# TIDA-010933-DCDC-CLLLC.net
KiCad netlist of a schematic drawn in Altium Designer
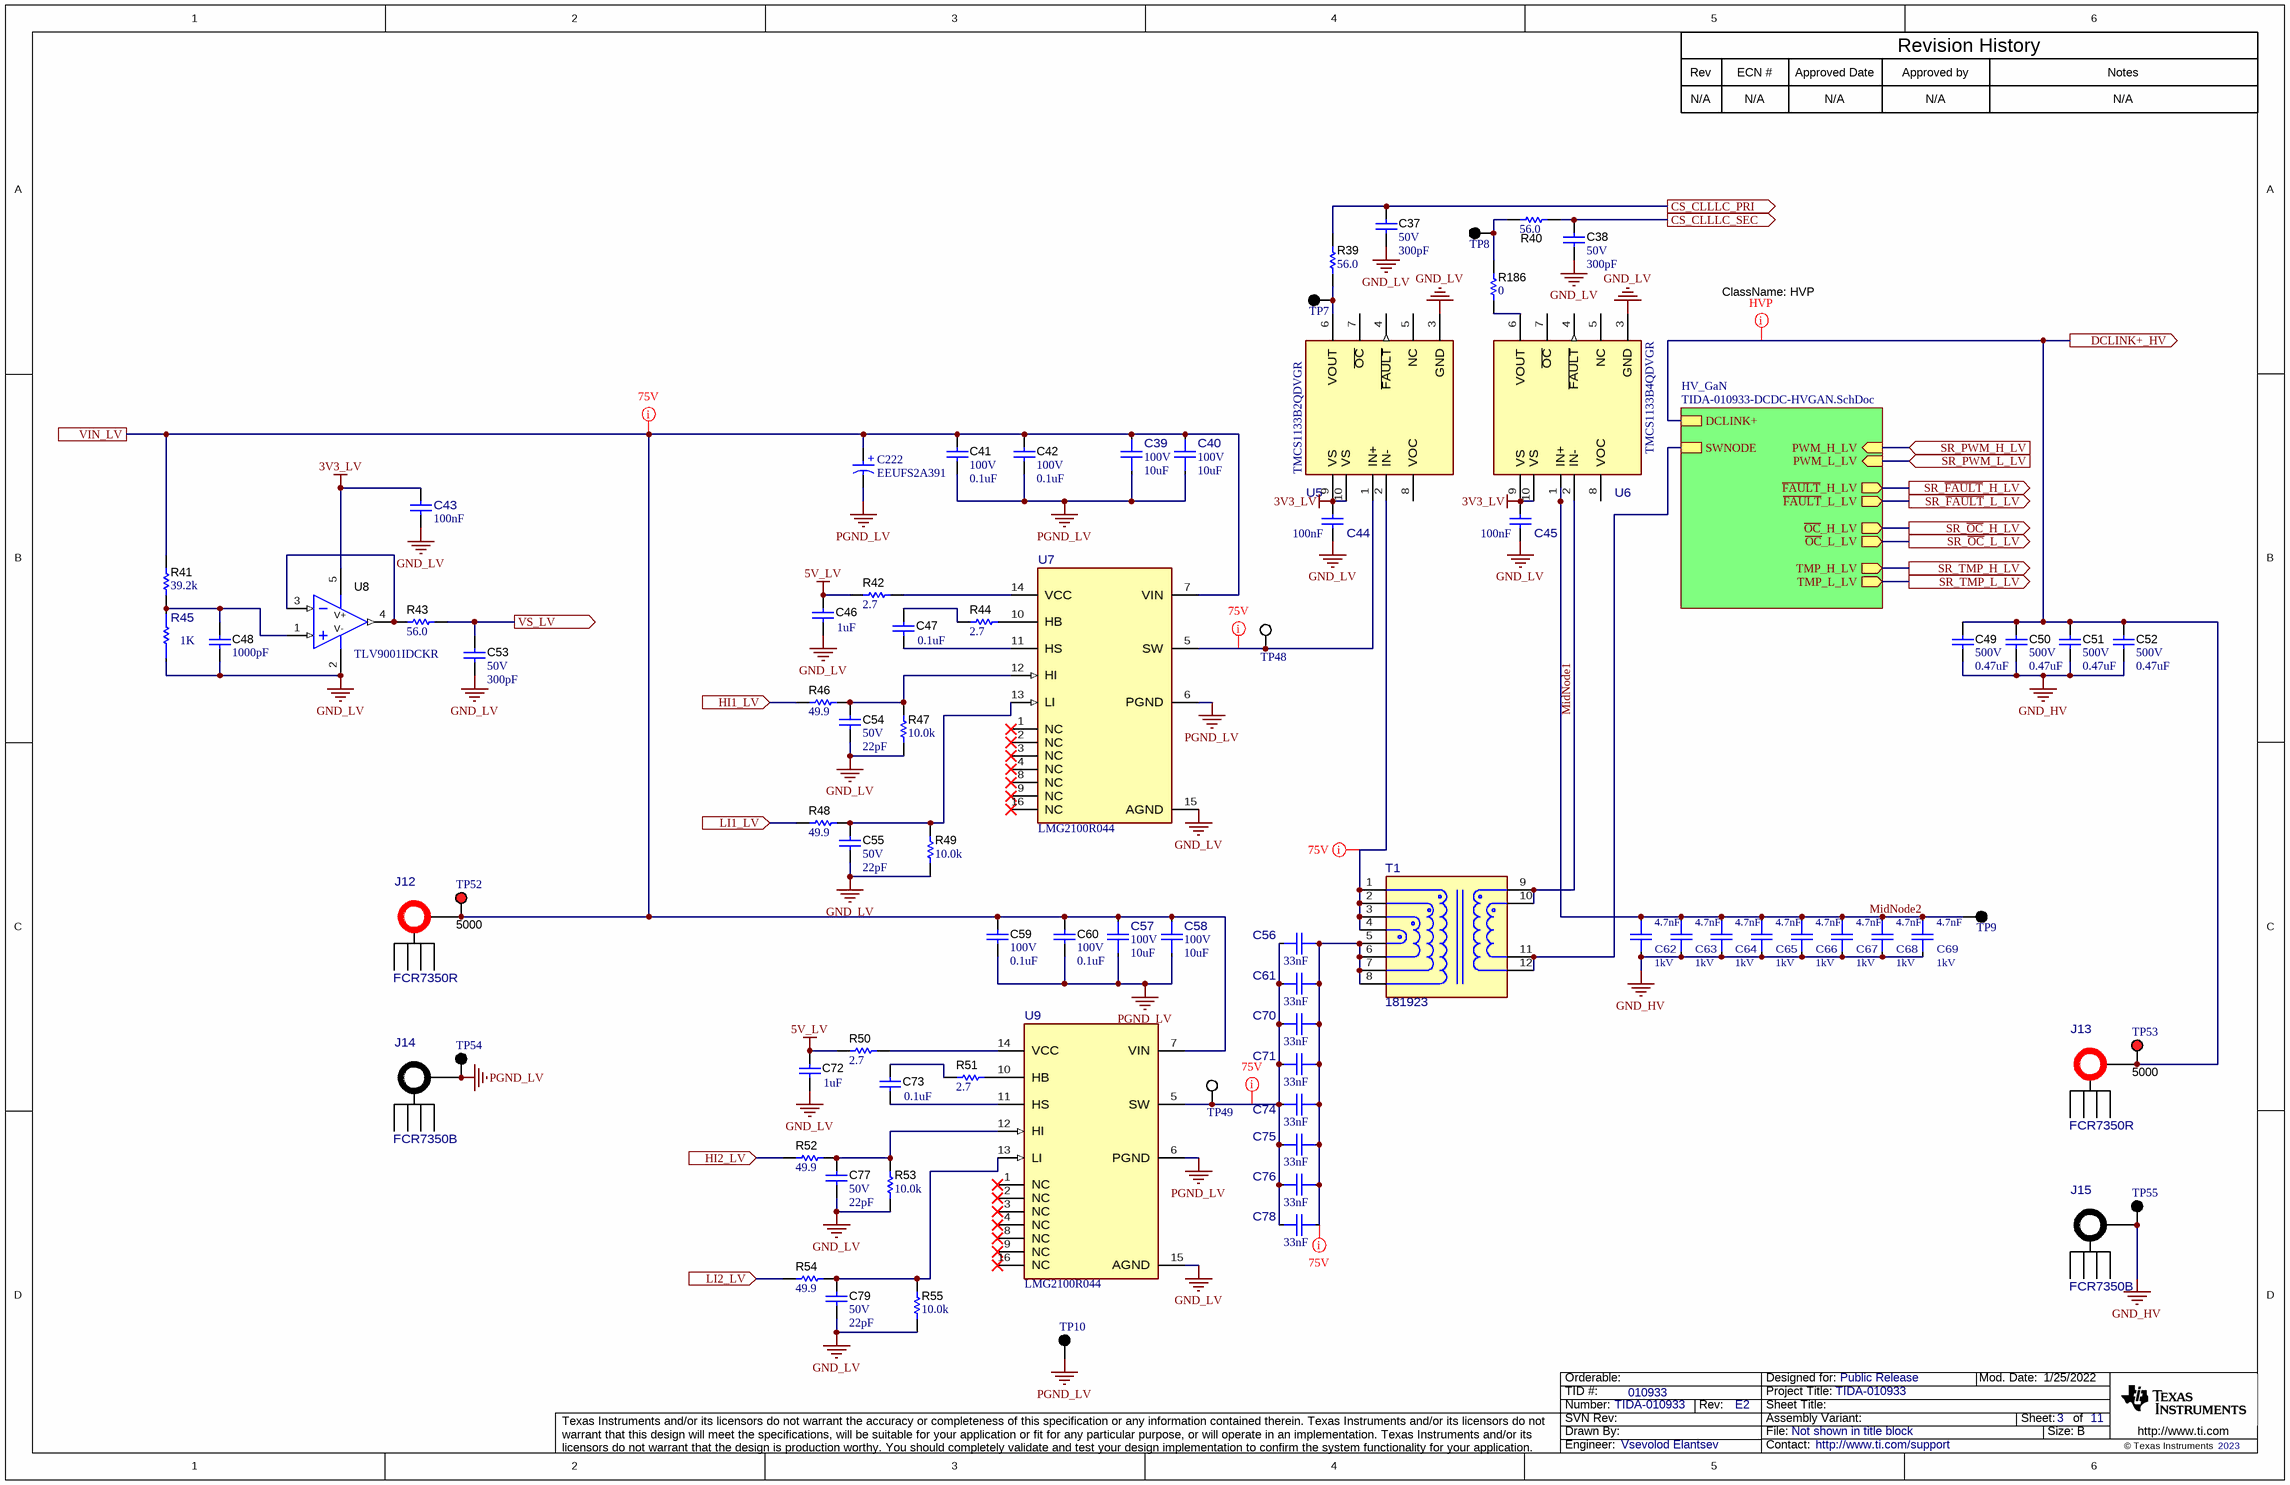
[diagram p0: TIDA-010933-DCDC-CLLLC.SchDoc]

(export (version "E")
  (design (tool "Eeschema 10.0.6"))
  (components
    (comp (ref "C37")
      (value "GRM1555C1H301JA01D")
      (footprint "0402")
      (description "CAP, CERM, 300 pF, 50 V, +/- 5%, C0G/NP0, 0402")
      (fields
        (field (name "MANUFACTURER") "MuRata")
        (field (name "VDC_V") "50V")
        (field (name "VALUEDISPLAYED") "300pF")
        (field (name "PUBLISHER") "Texas Instruments")
      )
      (libsource (lib "Altium Vault - TI") (part "Capacitor"))
    )
    (comp (ref "C38")
      (value "GRM1555C1H301JA01D")
      (footprint "0402")
      (description "CAP, CERM, 300 pF, 50 V, +/- 5%, C0G/NP0, 0402")
      (fields
        (field (name "MANUFACTURER") "MuRata")
        (field (name "VDC_V") "50V")
        (field (name "VALUEDISPLAYED") "300pF")
        (field (name "PUBLISHER") "Texas Instruments")
      )
      (libsource (lib "Altium Vault - TI") (part "Capacitor"))
    )
    (comp (ref "C39")
      (value "C3225X7R2A106K250AC")
      (footprint "FP-C3225X7R2A106K250AC_1210-MFG")
      (description "10 µF ±10% 100V Ceramic Capacitor X7R 1210 (3225 Metric)")
      (fields
        (field (name "DIGIKEY PART NUMBER") "445-C3225X7R2A106K250ACCT-ND")
        (field (name "MOUSER PART NUMBER") "810-C3225X7R2A106K25")
        (field (name "VDC_V") "100V")
        (field (name "VALUEDISPLAYED") "10uF")
      )
      (libsource (lib "Altium Vault - TI") (part "SYM-C3225X7R2A106K250AC"))
    )
    (comp (ref "C40")
      (value "C3225X7R2A106K250AC")
      (footprint "FP-C3225X7R2A106K250AC_1210-MFG")
      (description "10 µF ±10% 100V Ceramic Capacitor X7R 1210 (3225 Metric)")
      (fields
        (field (name "DIGIKEY PART NUMBER") "445-C3225X7R2A106K250ACCT-ND")
        (field (name "MOUSER PART NUMBER") "810-C3225X7R2A106K25")
        (field (name "VDC_V") "100V")
        (field (name "VALUEDISPLAYED") "10uF")
      )
      (libsource (lib "Altium Vault - TI") (part "SYM-C3225X7R2A106K250AC"))
    )
    (comp (ref "C41")
      (value "GRM155R62A104KE14D")
      (footprint "0402")
      (description "CAP, CERM, 0.1 uF, 100 V, +/- 10%, X5R, 0402")
      (fields
        (field (name "MANUFACTURER") "MuRata")
        (field (name "VDC_V") "100V")
        (field (name "VALUEDISPLAYED") "0.1uF")
        (field (name "PUBLISHER") "Texas Instruments")
      )
      (libsource (lib "Altium Vault - TI") (part "Capacitor"))
    )
    (comp (ref "C42")
      (value "GRM155R62A104KE14D")
      (footprint "0402")
      (description "CAP, CERM, 0.1 uF, 100 V, +/- 10%, X5R, 0402")
      (fields
        (field (name "MANUFACTURER") "MuRata")
        (field (name "VDC_V") "100V")
        (field (name "VALUEDISPLAYED") "0.1uF")
        (field (name "PUBLISHER") "Texas Instruments")
      )
      (libsource (lib "Altium Vault - TI") (part "Capacitor"))
    )
    (comp (ref "C43")
      (value "CL10B104KB8NNNC")
      (footprint "FP-CL10B104KB8NNNC_0603-IPC_B")
      (description "CAP CER 0.1UF 50V X7R 0603")
      (fields (field (name "CAP_F") "100nF") (field (name "MANUFACTURER") "Samsung"))
      (libsource (lib "Altium Vault - TI") (part "SYM-CAPACITOR"))
    )
    (comp (ref "C44")
      (value "CL10B104KB8NNNC")
      (footprint "FP-CL10B104KB8NNNC_0603-IPC_B")
      (description "CAP CER 0.1UF 50V X7R 0603")
      (fields (field (name "CAP_F") "100nF") (field (name "MANUFACTURER") "Samsung"))
      (libsource (lib "Altium Vault - TI") (part "SYM-CAPACITOR"))
    )
    (comp (ref "C45")
      (value "CL10B104KB8NNNC")
      (footprint "FP-CL10B104KB8NNNC_0603-IPC_B")
      (description "CAP CER 0.1UF 50V X7R 0603")
      (fields (field (name "CAP_F") "100nF") (field (name "MANUFACTURER") "Samsung"))
      (libsource (lib "Altium Vault - TI") (part "SYM-CAPACITOR"))
    )
    (comp (ref "C46")
      (value "GRM155R61E105KA12D")
      (footprint "0402")
      (description "CAP, CERM, 1 uF, 25 V, +/- 10%, X5R, 0402")
      (fields
        (field (name "MANUFACTURER") "MuRata")
        (field (name "VALUEDISPLAYED") "1uF")
        (field (name "PUBLISHER") "Texas Instruments")
      )
      (libsource (lib "Altium Vault - TI") (part "Capacitor"))
    )
    (comp (ref "C47")
      (value "GRM155R71E104KE14D")
      (footprint "0402")
      (description "CAP, CERM, 0.1 uF, 25 V, +/- 10%, X7R, 0402")
      (fields
        (field (name "MANUFACTURER") "MuRata")
        (field (name "VALUEDISPLAYED") "0.1uF")
        (field (name "PUBLISHER") "Texas Instruments")
      )
      (libsource (lib "Altium Vault - TI") (part "Capacitor"))
    )
    (comp (ref "C48")
      (value "CC0603JRNPO8BN102")
      (footprint "0603")
      (description "CAP, CERM, 1000 pF, 25 V,+/- 5%, C0G/NP0, 0603")
      (fields (field (name "VALUEDISPLAYED") "1000pF") (field (name "MANUFACTURER") "Yageo"))
      (libsource (lib "Altium Vault - TI") (part "Capacitor"))
    )
    (comp (ref "C49")
      (value "1812Y5000474KXTWS2")
      (footprint "1812_254")
      (description "CAP, CERM, 0.47 uF, 500 V, +/- 10%, X7R, 1812")
      (fields
        (field (name "MANUFACTURER") "Knowles Capacitors")
        (field (name "VDC_V") "500V")
        (field (name "VALUEDISPLAYED") "0.47uF")
        (field (name "PUBLISHER") "Texas Instruments")
      )
      (libsource (lib "Altium Vault - TI") (part "Capacitor"))
    )
    (comp (ref "C50")
      (value "1812Y5000474KXTWS2")
      (footprint "1812_254")
      (description "CAP, CERM, 0.47 uF, 500 V, +/- 10%, X7R, 1812")
      (fields
        (field (name "MANUFACTURER") "Knowles Capacitors")
        (field (name "VDC_V") "500V")
        (field (name "VALUEDISPLAYED") "0.47uF")
        (field (name "PUBLISHER") "Texas Instruments")
      )
      (libsource (lib "Altium Vault - TI") (part "Capacitor"))
    )
    (comp (ref "C51")
      (value "1812Y5000474KXTWS2")
      (footprint "1812_254")
      (description "CAP, CERM, 0.47 uF, 500 V, +/- 10%, X7R, 1812")
      (fields
        (field (name "MANUFACTURER") "Knowles Capacitors")
        (field (name "VDC_V") "500V")
        (field (name "VALUEDISPLAYED") "0.47uF")
        (field (name "PUBLISHER") "Texas Instruments")
      )
      (libsource (lib "Altium Vault - TI") (part "Capacitor"))
    )
    (comp (ref "C52")
      (value "1812Y5000474KXTWS2")
      (footprint "1812_254")
      (description "CAP, CERM, 0.47 uF, 500 V, +/- 10%, X7R, 1812")
      (fields
        (field (name "MANUFACTURER") "Knowles Capacitors")
        (field (name "VDC_V") "500V")
        (field (name "VALUEDISPLAYED") "0.47uF")
        (field (name "PUBLISHER") "Texas Instruments")
      )
      (libsource (lib "Altium Vault - TI") (part "Capacitor"))
    )
    (comp (ref "C53")
      (value "GRM1555C1H301JA01D")
      (footprint "0402")
      (description "CAP, CERM, 300 pF, 50 V, +/- 5%, C0G/NP0, 0402")
      (fields
        (field (name "MANUFACTURER") "MuRata")
        (field (name "VDC_V") "50V")
        (field (name "VALUEDISPLAYED") "300pF")
        (field (name "PUBLISHER") "Texas Instruments")
      )
      (libsource (lib "Altium Vault - TI") (part "Capacitor"))
    )
    (comp (ref "C54")
      (value "CC0402JRNPO9BN220")
      (footprint "0402")
      (description "CAP, CERM, 22 pF, 50 V,+/- 5%, C0G/NP0, 0402")
      (fields
        (field (name "VDC_V") "50V")
        (field (name "MANUFACTURER") "Yageo")
        (field (name "VALUEDISPLAYED") "22pF")
      )
      (libsource (lib "Altium Vault - TI") (part "Capacitor"))
    )
    (comp (ref "C55")
      (value "CC0402JRNPO9BN220")
      (footprint "0402")
      (description "CAP, CERM, 22 pF, 50 V,+/- 5%, C0G/NP0, 0402")
      (fields
        (field (name "VDC_V") "50V")
        (field (name "MANUFACTURER") "Yageo")
        (field (name "VALUEDISPLAYED") "22pF")
      )
      (libsource (lib "Altium Vault - TI") (part "Capacitor"))
    )
    (comp (ref "C56")
      (value "C3225C0G2A333J200AA")
      (footprint "FP-C3225C0G2A333J200AA_1210-MFG")
      (description "Multilayer Ceramic Capacitors 33nF ±5% 100V C0G SMD 1210")
      (fields (field (name "MANUFACTURER") "TDK") (field (name "VALUEDISPLAYED") "33nF"))
      (libsource (lib "Altium Vault - TI") (part "SYM-C3225C0G2A333J200AA"))
    )
    (comp (ref "C57")
      (value "C3225X7R2A106K250AC")
      (footprint "FP-C3225X7R2A106K250AC_1210-MFG")
      (description "10 µF ±10% 100V Ceramic Capacitor X7R 1210 (3225 Metric)")
      (fields
        (field (name "DIGIKEY PART NUMBER") "445-C3225X7R2A106K250ACCT-ND")
        (field (name "MOUSER PART NUMBER") "810-C3225X7R2A106K25")
        (field (name "VDC_V") "100V")
        (field (name "VALUEDISPLAYED") "10uF")
      )
      (libsource (lib "Altium Vault - TI") (part "SYM-C3225X7R2A106K250AC"))
    )
    (comp (ref "C58")
      (value "C3225X7R2A106K250AC")
      (footprint "FP-C3225X7R2A106K250AC_1210-MFG")
      (description "10 µF ±10% 100V Ceramic Capacitor X7R 1210 (3225 Metric)")
      (fields
        (field (name "DIGIKEY PART NUMBER") "445-C3225X7R2A106K250ACCT-ND")
        (field (name "MOUSER PART NUMBER") "810-C3225X7R2A106K25")
        (field (name "VDC_V") "100V")
        (field (name "VALUEDISPLAYED") "10uF")
      )
      (libsource (lib "Altium Vault - TI") (part "SYM-C3225X7R2A106K250AC"))
    )
    (comp (ref "C59")
      (value "GRM155R62A104KE14D")
      (footprint "0402")
      (description "CAP, CERM, 0.1 uF, 100 V, +/- 10%, X5R, 0402")
      (fields
        (field (name "MANUFACTURER") "MuRata")
        (field (name "VDC_V") "100V")
        (field (name "VALUEDISPLAYED") "0.1uF")
        (field (name "PUBLISHER") "Texas Instruments")
      )
      (libsource (lib "Altium Vault - TI") (part "Capacitor"))
    )
    (comp (ref "C60")
      (value "GRM155R62A104KE14D")
      (footprint "0402")
      (description "CAP, CERM, 0.1 uF, 100 V, +/- 10%, X5R, 0402")
      (fields
        (field (name "MANUFACTURER") "MuRata")
        (field (name "VDC_V") "100V")
        (field (name "VALUEDISPLAYED") "0.1uF")
        (field (name "PUBLISHER") "Texas Instruments")
      )
      (libsource (lib "Altium Vault - TI") (part "Capacitor"))
    )
    (comp (ref "C61")
      (value "C3225C0G2A333J200AA")
      (footprint "FP-C3225C0G2A333J200AA_1210-MFG")
      (description "Multilayer Ceramic Capacitors 33nF ±5% 100V C0G SMD 1210")
      (fields (field (name "MANUFACTURER") "TDK") (field (name "VALUEDISPLAYED") "33nF"))
      (libsource (lib "Altium Vault - TI") (part "SYM-C3225C0G2A333J200AA"))
    )
    (comp (ref "C62")
      (value "C3225C0G3A472J200AC")
      (footprint "FP-C3225C0G3A472J200AC_1210-MFG")
      (description "Multilayer Ceramic Capacitors 4.7nF ±5% 1000V C0G SMD 1210")
      (fields
        (field (name "MANUFACTURER") "TDK")
        (field (name "VALUEDISPLAYED") "4.7nF")
        (field (name "VDC_V") "1kV")
      )
      (libsource (lib "Altium Vault - TI") (part "SYM-C3225C0G3A472J200AC"))
    )
    (comp (ref "C63")
      (value "C3225C0G3A472J200AC")
      (footprint "FP-C3225C0G3A472J200AC_1210-MFG")
      (description "Multilayer Ceramic Capacitors 4.7nF ±5% 1000V C0G SMD 1210")
      (fields
        (field (name "MANUFACTURER") "TDK")
        (field (name "VALUEDISPLAYED") "4.7nF")
        (field (name "VDC_V") "1kV")
      )
      (libsource (lib "Altium Vault - TI") (part "SYM-C3225C0G3A472J200AC"))
    )
    (comp (ref "C64")
      (value "C3225C0G3A472J200AC")
      (footprint "FP-C3225C0G3A472J200AC_1210-MFG")
      (description "Multilayer Ceramic Capacitors 4.7nF ±5% 1000V C0G SMD 1210")
      (fields
        (field (name "MANUFACTURER") "TDK")
        (field (name "VALUEDISPLAYED") "4.7nF")
        (field (name "VDC_V") "1kV")
      )
      (libsource (lib "Altium Vault - TI") (part "SYM-C3225C0G3A472J200AC"))
    )
    (comp (ref "C65")
      (value "C3225C0G3A472J200AC")
      (footprint "FP-C3225C0G3A472J200AC_1210-MFG")
      (description "Multilayer Ceramic Capacitors 4.7nF ±5% 1000V C0G SMD 1210")
      (fields
        (field (name "MANUFACTURER") "TDK")
        (field (name "VALUEDISPLAYED") "4.7nF")
        (field (name "VDC_V") "1kV")
      )
      (libsource (lib "Altium Vault - TI") (part "SYM-C3225C0G3A472J200AC"))
    )
    (comp (ref "C66")
      (value "C3225C0G3A472J200AC")
      (footprint "FP-C3225C0G3A472J200AC_1210-MFG")
      (description "Multilayer Ceramic Capacitors 4.7nF ±5% 1000V C0G SMD 1210")
      (fields
        (field (name "MANUFACTURER") "TDK")
        (field (name "VALUEDISPLAYED") "4.7nF")
        (field (name "VDC_V") "1kV")
      )
      (libsource (lib "Altium Vault - TI") (part "SYM-C3225C0G3A472J200AC"))
    )
    (comp (ref "C67")
      (value "C3225C0G3A472J200AC")
      (footprint "FP-C3225C0G3A472J200AC_1210-MFG")
      (description "Multilayer Ceramic Capacitors 4.7nF ±5% 1000V C0G SMD 1210")
      (fields
        (field (name "MANUFACTURER") "TDK")
        (field (name "VALUEDISPLAYED") "4.7nF")
        (field (name "VDC_V") "1kV")
      )
      (libsource (lib "Altium Vault - TI") (part "SYM-C3225C0G3A472J200AC"))
    )
    (comp (ref "C68")
      (value "C3225C0G3A472J200AC")
      (footprint "FP-C3225C0G3A472J200AC_1210-MFG")
      (description "Multilayer Ceramic Capacitors 4.7nF ±5% 1000V C0G SMD 1210")
      (fields
        (field (name "MANUFACTURER") "TDK")
        (field (name "VALUEDISPLAYED") "4.7nF")
        (field (name "VDC_V") "1kV")
      )
      (libsource (lib "Altium Vault - TI") (part "SYM-C3225C0G3A472J200AC"))
    )
    (comp (ref "C69")
      (value "C3225C0G3A472J200AC")
      (footprint "FP-C3225C0G3A472J200AC_1210-MFG")
      (description "Multilayer Ceramic Capacitors 4.7nF ±5% 1000V C0G SMD 1210")
      (fields
        (field (name "MANUFACTURER") "TDK")
        (field (name "VALUEDISPLAYED") "4.7nF")
        (field (name "VDC_V") "1kV")
      )
      (libsource (lib "Altium Vault - TI") (part "SYM-C3225C0G3A472J200AC"))
    )
    (comp (ref "C70")
      (value "C3225C0G2A333J200AA")
      (footprint "FP-C3225C0G2A333J200AA_1210-MFG")
      (description "Multilayer Ceramic Capacitors 33nF ±5% 100V C0G SMD 1210")
      (fields (field (name "MANUFACTURER") "TDK") (field (name "VALUEDISPLAYED") "33nF"))
      (libsource (lib "Altium Vault - TI") (part "SYM-C3225C0G2A333J200AA"))
    )
    (comp (ref "C71")
      (value "C3225C0G2A333J200AA")
      (footprint "FP-C3225C0G2A333J200AA_1210-MFG")
      (description "Multilayer Ceramic Capacitors 33nF ±5% 100V C0G SMD 1210")
      (fields (field (name "MANUFACTURER") "TDK") (field (name "VALUEDISPLAYED") "33nF"))
      (libsource (lib "Altium Vault - TI") (part "SYM-C3225C0G2A333J200AA"))
    )
    (comp (ref "C72")
      (value "GRM155R61E105KA12D")
      (footprint "0402")
      (description "CAP, CERM, 1 uF, 25 V, +/- 10%, X5R, 0402")
      (fields
        (field (name "MANUFACTURER") "MuRata")
        (field (name "VALUEDISPLAYED") "1uF")
        (field (name "PUBLISHER") "Texas Instruments")
      )
      (libsource (lib "Altium Vault - TI") (part "Capacitor"))
    )
    (comp (ref "C73")
      (value "GRM155R71E104KE14D")
      (footprint "0402")
      (description "CAP, CERM, 0.1 uF, 25 V, +/- 10%, X7R, 0402")
      (fields
        (field (name "MANUFACTURER") "MuRata")
        (field (name "VALUEDISPLAYED") "0.1uF")
        (field (name "PUBLISHER") "Texas Instruments")
      )
      (libsource (lib "Altium Vault - TI") (part "Capacitor"))
    )
    (comp (ref "C74")
      (value "C3225C0G2A333J200AA")
      (footprint "FP-C3225C0G2A333J200AA_1210-MFG")
      (description "Multilayer Ceramic Capacitors 33nF ±5% 100V C0G SMD 1210")
      (fields (field (name "MANUFACTURER") "TDK") (field (name "VALUEDISPLAYED") "33nF"))
      (libsource (lib "Altium Vault - TI") (part "SYM-C3225C0G2A333J200AA"))
    )
    (comp (ref "C75")
      (value "C3225C0G2A333J200AA")
      (footprint "FP-C3225C0G2A333J200AA_1210-MFG")
      (description "Multilayer Ceramic Capacitors 33nF ±5% 100V C0G SMD 1210")
      (fields (field (name "MANUFACTURER") "TDK") (field (name "VALUEDISPLAYED") "33nF"))
      (libsource (lib "Altium Vault - TI") (part "SYM-C3225C0G2A333J200AA"))
    )
    (comp (ref "C76")
      (value "C3225C0G2A333J200AA")
      (footprint "FP-C3225C0G2A333J200AA_1210-MFG")
      (description "Multilayer Ceramic Capacitors 33nF ±5% 100V C0G SMD 1210")
      (fields (field (name "MANUFACTURER") "TDK") (field (name "VALUEDISPLAYED") "33nF"))
      (libsource (lib "Altium Vault - TI") (part "SYM-C3225C0G2A333J200AA"))
    )
    (comp (ref "C77")
      (value "CC0402JRNPO9BN220")
      (footprint "0402")
      (description "CAP, CERM, 22 pF, 50 V,+/- 5%, C0G/NP0, 0402")
      (fields
        (field (name "VDC_V") "50V")
        (field (name "MANUFACTURER") "Yageo")
        (field (name "VALUEDISPLAYED") "22pF")
      )
      (libsource (lib "Altium Vault - TI") (part "Capacitor"))
    )
    (comp (ref "C78")
      (value "C3225C0G2A333J200AA")
      (footprint "FP-C3225C0G2A333J200AA_1210-MFG")
      (description "Multilayer Ceramic Capacitors 33nF ±5% 100V C0G SMD 1210")
      (fields (field (name "MANUFACTURER") "TDK") (field (name "VALUEDISPLAYED") "33nF"))
      (libsource (lib "Altium Vault - TI") (part "SYM-C3225C0G2A333J200AA"))
    )
    (comp (ref "C79")
      (value "CC0402JRNPO9BN220")
      (footprint "0402")
      (description "CAP, CERM, 22 pF, 50 V,+/- 5%, C0G/NP0, 0402")
      (fields
        (field (name "VDC_V") "50V")
        (field (name "MANUFACTURER") "Yageo")
        (field (name "VALUEDISPLAYED") "22pF")
      )
      (libsource (lib "Altium Vault - TI") (part "Capacitor"))
    )
    (comp (ref "C222")
      (value "EEUFS2A391")
      (footprint "WCAP-ATUL_D16H25")
      (description "WCAP-ATUL Aluminum Electrolytic Capacitor, Radial, THT, D16 x H25mm, 270µF, 100V")
      (fields (field (name "MANUFACTURER") "Panasonic"))
      (libsource (lib "Altium Vault - TI") (part "865230657014"))
    )
    (comp (ref "J12")
      (value "FCR7350R")
      (footprint "FP-FCR7350R_CONN_BANANA_JACK-MFG")
      (description "Banana Jack Connector Standard Banana Solder Red")
      (fields
        (field (name "MANUFACTURER") "CLIFF Electronic Components")
        (field (name "DIGIKEY PART NUMBER") "4654-FCR7350R-ND")
      )
      (libsource (lib "Altium Vault - TI") (part "SYM-FCR7350R"))
    )
    (comp (ref "J13")
      (value "FCR7350R")
      (footprint "FP-FCR7350R_CONN_BANANA_JACK-MFG")
      (description "Banana Jack Connector Standard Banana Solder Red")
      (fields
        (field (name "MANUFACTURER") "CLIFF Electronic Components")
        (field (name "DIGIKEY PART NUMBER") "4654-FCR7350R-ND")
      )
      (libsource (lib "Altium Vault - TI") (part "SYM-FCR7350R"))
    )
    (comp (ref "J14")
      (value "FCR7350B")
      (footprint "FP-FCR7350B_CONN_BANANA_JACK-MFG")
      (description "Banana Jack Connector Standard Banana Solder Black")
      (fields
        (field (name "MANUFACTURER") "CLIFF Electronic Components")
        (field (name "DIGIKEY PART NUMBER") "4654-FCR7350B-ND")
      )
      (libsource (lib "Altium Vault - TI") (part "SYM-FCR7350B"))
    )
    (comp (ref "J15")
      (value "FCR7350B")
      (footprint "FP-FCR7350B_CONN_BANANA_JACK-MFG")
      (description "Banana Jack Connector Standard Banana Solder Black")
      (fields
        (field (name "MANUFACTURER") "CLIFF Electronic Components")
        (field (name "DIGIKEY PART NUMBER") "4654-FCR7350B-ND")
      )
      (libsource (lib "Altium Vault - TI") (part "SYM-FCR7350B"))
    )
    (comp (ref "R39")
      (value "RC0603FR-0756RL")
      (footprint "0603")
      (description "RES, 56.0, 1%, 0.1 W, 0603")
      (fields (field (name "MANUFACTURER") "Yageo") (field (name "VALUEDISPLAYED") "56.0"))
      (libsource (lib "Altium Vault - TI") (part "Resistor"))
    )
    (comp (ref "R40")
      (value "RC0603FR-0756RL")
      (footprint "0603")
      (description "RES, 56.0, 1%, 0.1 W, 0603")
      (fields (field (name "MANUFACTURER") "Yageo") (field (name "VALUEDISPLAYED") "56.0"))
      (libsource (lib "Altium Vault - TI") (part "Resistor"))
    )
    (comp (ref "R41")
      (value "RT0603BRD0739K2L")
      (footprint "0603")
      (description "RES, 39.2 k, 0.1%, 0.1 W, 0603")
      (fields
        (field (name "MANUFACTURER") "Yageo America")
        (field (name "VALUEDISPLAYED") "39.2k")
        (field (name "PUBLISHER") "Texas Instruments")
      )
      (libsource (lib "Altium Vault - TI") (part "Resistor"))
    )
    (comp (ref "R42")
      (value "CRCW04022R70JNED")
      (footprint "0402")
      (description "RES, 2.7, 5%, 0.063 W, AEC-Q200 Grade 0, 0402")
      (fields (field (name "MANUFACTURER") "Vishay-Dale") (field (name "VALUEDISPLAYED") "2.7"))
      (libsource (lib "Altium Vault - TI") (part "Resistor"))
    )
    (comp (ref "R43")
      (value "RC0603FR-0756RL")
      (footprint "0603")
      (description "RES, 56.0, 1%, 0.1 W, 0603")
      (fields (field (name "MANUFACTURER") "Yageo") (field (name "VALUEDISPLAYED") "56.0"))
      (libsource (lib "Altium Vault - TI") (part "Resistor"))
    )
    (comp (ref "R44")
      (value "CRCW04022R70JNED")
      (footprint "0402")
      (description "RES, 2.7, 5%, 0.063 W, AEC-Q200 Grade 0, 0402")
      (fields (field (name "MANUFACTURER") "Vishay-Dale") (field (name "VALUEDISPLAYED") "2.7"))
      (libsource (lib "Altium Vault - TI") (part "Resistor"))
    )
    (comp (ref "R45")
      (value "1K")
      (footprint "FP-RT0603BRD071KL_0603-MFG")
      (description "High Precision-High Stability Chip Resistor Thin Film 0603 1kOhm 0.1% Paper T/R")
      (fields (field (name "MANUFACTURER") "Yageo") (field (name "DIGIKEY PART NUMBER") "YAG1237CT-ND"))
      (libsource (lib "Altium Vault - TI") (part "SYM-RT0603BRD071KL"))
    )
    (comp (ref "R46")
      (value "RC0402FR-0749R9L")
      (footprint "0402")
      (description "RES, 49.9, 1%, 0.063 W, 0402")
      (fields
        (field (name "MANUFACTURER") "Yageo America")
        (field (name "VALUEDISPLAYED") "49.9")
        (field (name "PUBLISHER") "Texas Instruments")
      )
      (libsource (lib "Altium Vault - TI") (part "Resistor"))
    )
    (comp (ref "R47")
      (value "RC0402FR-0710KL")
      (footprint "0402")
      (description "RES, 10.0 k, 1%, 0.063 W, 0402")
      (fields (field (name "MANUFACTURER") "Yageo America") (field (name "VALUEDISPLAYED") "10.0k"))
      (libsource (lib "Altium Vault - TI") (part "Resistor"))
    )
    (comp (ref "R48")
      (value "RC0402FR-0749R9L")
      (footprint "0402")
      (description "RES, 49.9, 1%, 0.063 W, 0402")
      (fields
        (field (name "MANUFACTURER") "Yageo America")
        (field (name "VALUEDISPLAYED") "49.9")
        (field (name "PUBLISHER") "Texas Instruments")
      )
      (libsource (lib "Altium Vault - TI") (part "Resistor"))
    )
    (comp (ref "R49")
      (value "RC0402FR-0710KL")
      (footprint "0402")
      (description "RES, 10.0 k, 1%, 0.063 W, 0402")
      (fields (field (name "MANUFACTURER") "Yageo America") (field (name "VALUEDISPLAYED") "10.0k"))
      (libsource (lib "Altium Vault - TI") (part "Resistor"))
    )
    (comp (ref "R50")
      (value "CRCW04022R70JNED")
      (footprint "0402")
      (description "RES, 2.7, 5%, 0.063 W, AEC-Q200 Grade 0, 0402")
      (fields (field (name "MANUFACTURER") "Vishay-Dale") (field (name "VALUEDISPLAYED") "2.7"))
      (libsource (lib "Altium Vault - TI") (part "Resistor"))
    )
    (comp (ref "R51")
      (value "CRCW04022R70JNED")
      (footprint "0402")
      (description "RES, 2.7, 5%, 0.063 W, AEC-Q200 Grade 0, 0402")
      (fields (field (name "MANUFACTURER") "Vishay-Dale") (field (name "VALUEDISPLAYED") "2.7"))
      (libsource (lib "Altium Vault - TI") (part "Resistor"))
    )
    (comp (ref "R52")
      (value "RC0402FR-0749R9L")
      (footprint "0402")
      (description "RES, 49.9, 1%, 0.063 W, 0402")
      (fields
        (field (name "MANUFACTURER") "Yageo America")
        (field (name "VALUEDISPLAYED") "49.9")
        (field (name "PUBLISHER") "Texas Instruments")
      )
      (libsource (lib "Altium Vault - TI") (part "Resistor"))
    )
    (comp (ref "R53")
      (value "RC0402FR-0710KL")
      (footprint "0402")
      (description "RES, 10.0 k, 1%, 0.063 W, 0402")
      (fields (field (name "MANUFACTURER") "Yageo America") (field (name "VALUEDISPLAYED") "10.0k"))
      (libsource (lib "Altium Vault - TI") (part "Resistor"))
    )
    (comp (ref "R54")
      (value "RC0402FR-0749R9L")
      (footprint "0402")
      (description "RES, 49.9, 1%, 0.063 W, 0402")
      (fields
        (field (name "MANUFACTURER") "Yageo America")
        (field (name "VALUEDISPLAYED") "49.9")
        (field (name "PUBLISHER") "Texas Instruments")
      )
      (libsource (lib "Altium Vault - TI") (part "Resistor"))
    )
    (comp (ref "R55")
      (value "RC0402FR-0710KL")
      (footprint "0402")
      (description "RES, 10.0 k, 1%, 0.063 W, 0402")
      (fields (field (name "MANUFACTURER") "Yageo America") (field (name "VALUEDISPLAYED") "10.0k"))
      (libsource (lib "Altium Vault - TI") (part "Resistor"))
    )
    (comp (ref "R186")
      (value "RC0603JR-070RL")
      (footprint "0603")
      (description "RES, 0, 5%, 0.1 W, 0603")
      (fields (field (name "MANUFACTURER") "Yageo") (field (name "VALUEDISPLAYED") "0"))
      (libsource (lib "Altium Vault - TI") (part "Resistor"))
    )
    (comp (ref "T1")
      (value "181923")
      (footprint "FP-181923_PTH_TRANSFORMER_74MM0_60MM0-MFG")
      (description "TRANSFORMER")
      (fields (field (name "MANUFACTURER") "Bourns"))
      (libsource (lib "Altium Vault - TI") (part "SYM-181923"))
    )
    (comp (ref "TP7")
      (value "5001")
      (footprint "Keystone5001")
      (description "Test Point, Miniature, Black, TH")
      (fields
        (field (name "MANUFACTURER") "Keystone Electronics")
        (field (name "PUBLISHER") "Texas Instruments")
      )
      (libsource (lib "Altium Vault - TI") (part "5001"))
    )
    (comp (ref "TP8")
      (value "5001")
      (footprint "Keystone5001")
      (description "Test Point, Miniature, Black, TH")
      (fields
        (field (name "MANUFACTURER") "Keystone Electronics")
        (field (name "PUBLISHER") "Texas Instruments")
      )
      (libsource (lib "Altium Vault - TI") (part "5001"))
    )
    (comp (ref "TP9")
      (value "5001")
      (footprint "Keystone5001")
      (description "Test Point, Miniature, Black, TH")
      (fields
        (field (name "MANUFACTURER") "Keystone Electronics")
        (field (name "PUBLISHER") "Texas Instruments")
      )
      (libsource (lib "Altium Vault - TI") (part "5001"))
    )
    (comp (ref "TP10")
      (value "5001")
      (footprint "Keystone5001")
      (description "Test Point, Miniature, Black, TH")
      (fields
        (field (name "MANUFACTURER") "Keystone Electronics")
        (field (name "PUBLISHER") "Texas Instruments")
      )
      (libsource (lib "Altium Vault - TI") (part "5001"))
    )
    (comp (ref "TP48")
      (value "5015")
      (footprint "Testpoint_Keystone_Miniature")
      (description "Test Point, Miniature, SMT")
      (fields
        (field (name "MANUFACTURER") "Keystone Electronics")
        (field (name "PUBLISHER") "Texas Instruments")
      )
      (libsource (lib "Altium Vault - TI") (part "5015"))
    )
    (comp (ref "TP49")
      (value "5015")
      (footprint "Testpoint_Keystone_Miniature")
      (description "Test Point, Miniature, SMT")
      (fields
        (field (name "MANUFACTURER") "Keystone Electronics")
        (field (name "PUBLISHER") "Texas Instruments")
      )
      (libsource (lib "Altium Vault - TI") (part "5015"))
    )
    (comp (ref "TP52")
      (value "5000")
      (footprint "Keystone5000")
      (description "Test Point, Miniature, Red, TH")
      (fields
        (field (name "MANUFACTURER") "Keystone Electronics")
        (field (name "PUBLISHER") "Texas Instruments")
      )
      (libsource (lib "Altium Vault - TI") (part "5000"))
    )
    (comp (ref "TP53")
      (value "5000")
      (footprint "Keystone5000")
      (description "Test Point, Miniature, Red, TH")
      (fields
        (field (name "MANUFACTURER") "Keystone Electronics")
        (field (name "PUBLISHER") "Texas Instruments")
      )
      (libsource (lib "Altium Vault - TI") (part "5000"))
    )
    (comp (ref "TP54")
      (value "5001")
      (footprint "Keystone5001")
      (description "Test Point, Miniature, Black, TH")
      (fields
        (field (name "MANUFACTURER") "Keystone Electronics")
        (field (name "PUBLISHER") "Texas Instruments")
      )
      (libsource (lib "Altium Vault - TI") (part "5001"))
    )
    (comp (ref "TP55")
      (value "5001")
      (footprint "Keystone5001")
      (description "Test Point, Miniature, Black, TH")
      (fields
        (field (name "MANUFACTURER") "Keystone Electronics")
        (field (name "PUBLISHER") "Texas Instruments")
      )
      (libsource (lib "Altium Vault - TI") (part "5001"))
    )
    (comp (ref "U5")
      (value "TMCS1133B2QDVGR")
      (footprint "DVG0010A-MFG")
      (fields (field (name "PARTNUMBER") "TMCS1133B2QDVGR") (field (name "MANUFACTURER") "Texas Instruments"))
      (libsource (lib "Altium Vault - TI") (part "SYM-TMCS1133B2QDVGR"))
    )
    (comp (ref "U6")
      (value "TMCS1133B4QDVGR")
      (footprint "DVG0010A-MFG")
      (fields (field (name "MANUFACTURER") "Texas Instruments") (field (name "PARTNUMBER") "TMCS1133B4QDVGR"))
      (libsource (lib "Altium Vault - TI") (part "SYM-TMCS1133B4QDVGR"))
    )
    (comp (ref "U7")
      (value "LMG2100R044")
      (footprint "VBN0016A-MFG")
      (description "100-V, 53-A GaN Half-Bridge Power Stage")
      (fields (field (name "MANUFACTURER") "Texas Instruments") (field (name "PARTNUMBER") "LMG2100R044"))
      (libsource (lib "Altium Vault - TI") (part "SYM-LMG2100R026"))
    )
    (comp (ref "U8")
      (value "TLV9001IDCKR")
      (footprint "DCK0005A_N")
      (description "Low-Power, Rail-to-Rail In and Out, 1-MHz Operational Amplifier, DCK0005A (SOT-SC70-5)")
      (fields
        (field (name "ALTERNATE PARTNUMBER") "TLV9001IDCKT")
        (field (name "MANUFACTURER") "Texas Instruments")
        (field (name "PARTNUMBER") "TLV9001IDCKR")
      )
      (libsource (lib "Altium Vault - TI") (part "OPAMP_SINGLE_SOT321"))
    )
    (comp (ref "U9")
      (value "LMG2100R044")
      (footprint "VBN0016A-MFG")
      (description "100-V, 53-A GaN Half-Bridge Power Stage")
      (fields (field (name "MANUFACTURER") "Texas Instruments") (field (name "PARTNUMBER") "LMG2100R044"))
      (libsource (lib "Altium Vault - TI") (part "SYM-LMG2100R026"))
    )
  )
  (nets
    (net (code "1") (name "/CS_CLLLC_PRI") (class "Default")
      (node (ref "C37") (pin "1") (pinfunction "1_1") (pintype "passive"))
      (node (ref "R39") (pin "2") (pinfunction "2_2") (pintype "passive"))
    )
    (net (code "2") (name "/CS_CLLLC_SEC") (class "Default")
      (node (ref "C38") (pin "1") (pinfunction "1_1") (pintype "passive"))
      (node (ref "R40") (pin "1") (pinfunction "1_1") (pintype "passive"))
    )
    (net (code "3") (name "/DCLINK+_HV") (class "Default")
      (node (ref "C49") (pin "1") (pinfunction "1_1") (pintype "passive"))
      (node (ref "C50") (pin "1") (pinfunction "1_1") (pintype "passive"))
      (node (ref "C51") (pin "1") (pinfunction "1_1") (pintype "passive"))
      (node (ref "C52") (pin "1") (pinfunction "1_1") (pintype "passive"))
      (node (ref "J13") (pin "1") (pinfunction "1_1") (pintype "passive"))
      (node (ref "TP53") (pin "1") (pintype "passive"))
    )
    (net (code "4") (name "/HI1_LV") (class "Default")
      (node (ref "R46") (pin "1") (pinfunction "1_1") (pintype "passive"))
    )
    (net (code "5") (name "/HI2_LV") (class "Default")
      (node (ref "R52") (pin "1") (pinfunction "1_1") (pintype "passive"))
    )
    (net (code "6") (name "/LI1_LV") (class "Default")
      (node (ref "R48") (pin "1") (pinfunction "1_1") (pintype "passive"))
    )
    (net (code "7") (name "/LI2_LV") (class "Default")
      (node (ref "R54") (pin "1") (pinfunction "1_1") (pintype "passive"))
    )
    (net (code "8") (name "/MidNode1") (class "Default")
      (node (ref "T1") (pin "10") (pinfunction "10_10") (pintype "passive"))
      (node (ref "T1") (pin "9") (pinfunction "9_9") (pintype "passive"))
      (node (ref "U6") (pin "2") (pinfunction "IN-_2") (pintype "passive"))
    )
    (net (code "9") (name "/MidNode2") (class "Default")
      (node (ref "C62") (pin "1") (pinfunction "1_1") (pintype "passive"))
      (node (ref "C63") (pin "1") (pinfunction "1_1") (pintype "passive"))
      (node (ref "C64") (pin "1") (pinfunction "1_1") (pintype "passive"))
      (node (ref "C65") (pin "1") (pinfunction "1_1") (pintype "passive"))
      (node (ref "C66") (pin "1") (pinfunction "1_1") (pintype "passive"))
      (node (ref "C67") (pin "1") (pinfunction "1_1") (pintype "passive"))
      (node (ref "C68") (pin "1") (pinfunction "1_1") (pintype "passive"))
      (node (ref "C69") (pin "1") (pinfunction "1_1") (pintype "passive"))
      (node (ref "TP9") (pin "1") (pintype "passive"))
      (node (ref "U6") (pin "1") (pinfunction "IN+_1") (pintype "passive"))
    )
    (net (code "18") (name "/SWNODE") (class "Default")
      (node (ref "T1") (pin "11") (pinfunction "11_11") (pintype "passive"))
      (node (ref "T1") (pin "12") (pinfunction "12_12") (pintype "passive"))
    )
    (net (code "19") (name "/VIN_LV") (class "Default")
      (node (ref "C222") (pin "1") (pinfunction "P_1") (pintype "passive"))
      (node (ref "C39") (pin "2") (pinfunction "2_2") (pintype "passive"))
      (node (ref "C40") (pin "2") (pinfunction "2_2") (pintype "passive"))
      (node (ref "C41") (pin "1") (pinfunction "1_1") (pintype "passive"))
      (node (ref "C42") (pin "1") (pinfunction "1_1") (pintype "passive"))
      (node (ref "C57") (pin "2") (pinfunction "2_2") (pintype "passive"))
      (node (ref "C58") (pin "2") (pinfunction "2_2") (pintype "passive"))
      (node (ref "C59") (pin "1") (pinfunction "1_1") (pintype "passive"))
      (node (ref "C60") (pin "1") (pinfunction "1_1") (pintype "passive"))
      (node (ref "J12") (pin "1") (pinfunction "1_1") (pintype "passive"))
      (node (ref "R41") (pin "2") (pinfunction "2_2") (pintype "passive"))
      (node (ref "TP52") (pin "1") (pintype "passive"))
      (node (ref "U7") (pin "7") (pinfunction "VIN_7") (pintype "power_in"))
      (node (ref "U9") (pin "7") (pinfunction "VIN_7") (pintype "power_in"))
    )
    (net (code "20") (name "/VS_LV") (class "Default")
      (node (ref "C53") (pin "1") (pinfunction "1_1") (pintype "passive"))
      (node (ref "R43") (pin "2") (pinfunction "2_2") (pintype "passive"))
    )
    (net (code "21") (name "3V3_LV") (class "Default")
      (node (ref "C43") (pin "1") (pinfunction "1_1") (pintype "passive"))
      (node (ref "C44") (pin "1") (pinfunction "1_1") (pintype "passive"))
      (node (ref "C45") (pin "1") (pinfunction "1_1") (pintype "passive"))
      (node (ref "U5") (pin "10") (pinfunction "VS_10") (pintype "power_in"))
      (node (ref "U5") (pin "9") (pinfunction "VS_9") (pintype "power_in"))
      (node (ref "U6") (pin "10") (pinfunction "VS_10") (pintype "power_in"))
      (node (ref "U6") (pin "9") (pinfunction "VS_9") (pintype "power_in"))
      (node (ref "U8") (pin "5") (pinfunction "V+_5") (pintype "power_in"))
    )
    (net (code "22") (name "5V_LV") (class "Default")
      (node (ref "C46") (pin "1") (pinfunction "1_1") (pintype "passive"))
      (node (ref "C72") (pin "1") (pinfunction "1_1") (pintype "passive"))
      (node (ref "R42") (pin "1") (pinfunction "1_1") (pintype "passive"))
      (node (ref "R50") (pin "1") (pinfunction "1_1") (pintype "passive"))
    )
    (net (code "23") (name "GND_HV") (class "Default")
      (node (ref "C49") (pin "2") (pinfunction "2_2") (pintype "passive"))
      (node (ref "C50") (pin "2") (pinfunction "2_2") (pintype "passive"))
      (node (ref "C51") (pin "2") (pinfunction "2_2") (pintype "passive"))
      (node (ref "C52") (pin "2") (pinfunction "2_2") (pintype "passive"))
      (node (ref "C62") (pin "2") (pinfunction "2_2") (pintype "passive"))
      (node (ref "C63") (pin "2") (pinfunction "2_2") (pintype "passive"))
      (node (ref "C64") (pin "2") (pinfunction "2_2") (pintype "passive"))
      (node (ref "C65") (pin "2") (pinfunction "2_2") (pintype "passive"))
      (node (ref "C66") (pin "2") (pinfunction "2_2") (pintype "passive"))
      (node (ref "C67") (pin "2") (pinfunction "2_2") (pintype "passive"))
      (node (ref "C68") (pin "2") (pinfunction "2_2") (pintype "passive"))
      (node (ref "C69") (pin "2") (pinfunction "2_2") (pintype "passive"))
      (node (ref "J15") (pin "1") (pinfunction "1_1") (pintype "passive"))
      (node (ref "TP55") (pin "1") (pintype "passive"))
    )
    (net (code "24") (name "GND_LV") (class "Default")
      (node (ref "C37") (pin "2") (pinfunction "2_2") (pintype "passive"))
      (node (ref "C38") (pin "2") (pinfunction "2_2") (pintype "passive"))
      (node (ref "C43") (pin "2") (pinfunction "2_2") (pintype "passive"))
      (node (ref "C44") (pin "2") (pinfunction "2_2") (pintype "passive"))
      (node (ref "C45") (pin "2") (pinfunction "2_2") (pintype "passive"))
      (node (ref "C46") (pin "2") (pinfunction "2_2") (pintype "passive"))
      (node (ref "C48") (pin "2") (pinfunction "2_2") (pintype "passive"))
      (node (ref "C53") (pin "2") (pinfunction "2_2") (pintype "passive"))
      (node (ref "C54") (pin "2") (pinfunction "2_2") (pintype "passive"))
      (node (ref "C55") (pin "2") (pinfunction "2_2") (pintype "passive"))
      (node (ref "C72") (pin "2") (pinfunction "2_2") (pintype "passive"))
      (node (ref "C77") (pin "2") (pinfunction "2_2") (pintype "passive"))
      (node (ref "C79") (pin "2") (pinfunction "2_2") (pintype "passive"))
      (node (ref "R45") (pin "1") (pinfunction "1_1") (pintype "passive"))
      (node (ref "R47") (pin "1") (pinfunction "1_1") (pintype "passive"))
      (node (ref "R49") (pin "1") (pinfunction "1_1") (pintype "passive"))
      (node (ref "R53") (pin "1") (pinfunction "1_1") (pintype "passive"))
      (node (ref "R55") (pin "1") (pinfunction "1_1") (pintype "passive"))
      (node (ref "U5") (pin "3") (pinfunction "GND_3") (pintype "power_in"))
      (node (ref "U6") (pin "3") (pinfunction "GND_3") (pintype "power_in"))
      (node (ref "U7") (pin "15") (pinfunction "AGND_15") (pintype "power_in"))
      (node (ref "U8") (pin "2") (pinfunction "V-_2") (pintype "power_in"))
      (node (ref "U9") (pin "15") (pinfunction "AGND_15") (pintype "power_in"))
    )
    (net (code "25") (name "Net-(C47-Pad1)") (class "Default")
      (node (ref "C47") (pin "1") (pinfunction "1_1") (pintype "passive"))
      (node (ref "R44") (pin "1") (pinfunction "1_1") (pintype "passive"))
    )
    (net (code "26") (name "Net-(C56-Pad1)") (class "Default")
      (node (ref "C56") (pin "1") (pinfunction "1_1") (pintype "passive"))
      (node (ref "C61") (pin "1") (pinfunction "1_1") (pintype "passive"))
      (node (ref "C70") (pin "1") (pinfunction "1_1") (pintype "passive"))
      (node (ref "C71") (pin "1") (pinfunction "1_1") (pintype "passive"))
      (node (ref "C74") (pin "1") (pinfunction "1_1") (pintype "passive"))
      (node (ref "C75") (pin "1") (pinfunction "1_1") (pintype "passive"))
      (node (ref "C76") (pin "1") (pinfunction "1_1") (pintype "passive"))
      (node (ref "C78") (pin "1") (pinfunction "1_1") (pintype "passive"))
      (node (ref "T1") (pin "5") (pinfunction "5_5") (pintype "passive"))
      (node (ref "T1") (pin "6") (pinfunction "6_6") (pintype "passive"))
      (node (ref "T1") (pin "7") (pinfunction "7_7") (pintype "passive"))
      (node (ref "T1") (pin "8") (pinfunction "8_8") (pintype "passive"))
    )
    (net (code "27") (name "Net-(C73-Pad1)") (class "Default")
      (node (ref "C73") (pin "1") (pinfunction "1_1") (pintype "passive"))
      (node (ref "R51") (pin "1") (pinfunction "1_1") (pintype "passive"))
    )
    (net (code "28") (name "Net-(R186-Pad2)") (class "Default")
      (node (ref "R186") (pin "2") (pinfunction "2_2") (pintype "passive"))
      (node (ref "R40") (pin "2") (pinfunction "2_2") (pintype "passive"))
      (node (ref "TP8") (pin "1") (pintype "passive"))
    )
    (net (code "29") (name "Net-(U5-IN+)") (class "Default")
      (node (ref "TP48") (pin "1") (pintype "passive"))
      (node (ref "U5") (pin "1") (pinfunction "IN+_1") (pintype "passive"))
      (node (ref "U7") (pin "5") (pinfunction "SW_5") (pintype "power_in"))
    )
    (net (code "30") (name "Net-(U5-IN-)") (class "Default")
      (node (ref "T1") (pin "1") (pinfunction "1_1") (pintype "passive"))
      (node (ref "T1") (pin "2") (pinfunction "2_2") (pintype "passive"))
      (node (ref "T1") (pin "3") (pinfunction "3_3") (pintype "passive"))
      (node (ref "T1") (pin "4") (pinfunction "4_4") (pintype "passive"))
      (node (ref "U5") (pin "2") (pinfunction "IN-_2") (pintype "passive"))
    )
    (net (code "31") (name "Net-(U5-VOUT)") (class "Default")
      (node (ref "R39") (pin "1") (pinfunction "1_1") (pintype "passive"))
      (node (ref "TP7") (pin "1") (pintype "passive"))
      (node (ref "U5") (pin "6") (pinfunction "VOUT_6") (pintype "passive"))
    )
    (net (code "32") (name "Net-(U6-VOUT)") (class "Default")
      (node (ref "R186") (pin "1") (pinfunction "1_1") (pintype "passive"))
      (node (ref "U6") (pin "6") (pinfunction "VOUT_6") (pintype "passive"))
    )
    (net (code "33") (name "Net-(U7-HB)") (class "Default")
      (node (ref "R44") (pin "2") (pinfunction "2_2") (pintype "passive"))
      (node (ref "U7") (pin "10") (pinfunction "HB_10") (pintype "power_in"))
    )
    (net (code "34") (name "Net-(U7-HI)") (class "Default")
      (node (ref "C54") (pin "1") (pinfunction "1_1") (pintype "passive"))
      (node (ref "R46") (pin "2") (pinfunction "2_2") (pintype "passive"))
      (node (ref "R47") (pin "2") (pinfunction "2_2") (pintype "passive"))
      (node (ref "U7") (pin "12") (pinfunction "HI_12") (pintype "input"))
    )
    (net (code "35") (name "Net-(U7-HS)") (class "Default")
      (node (ref "C47") (pin "2") (pinfunction "2_2") (pintype "passive"))
      (node (ref "U7") (pin "11") (pinfunction "HS_11") (pintype "power_in"))
    )
    (net (code "36") (name "Net-(U7-LI)") (class "Default")
      (node (ref "C55") (pin "1") (pinfunction "1_1") (pintype "passive"))
      (node (ref "R48") (pin "2") (pinfunction "2_2") (pintype "passive"))
      (node (ref "R49") (pin "2") (pinfunction "2_2") (pintype "passive"))
      (node (ref "U7") (pin "13") (pinfunction "LI_13") (pintype "input"))
    )
    (net (code "37") (name "Net-(U7-VCC)") (class "Default")
      (node (ref "R42") (pin "2") (pinfunction "2_2") (pintype "passive"))
      (node (ref "U7") (pin "14") (pinfunction "VCC_14") (pintype "power_in"))
    )
    (net (code "38") (name "Net-(U8-IN+)") (class "Default")
      (node (ref "C48") (pin "1") (pinfunction "1_1") (pintype "passive"))
      (node (ref "R41") (pin "1") (pinfunction "1_1") (pintype "passive"))
      (node (ref "R45") (pin "2") (pinfunction "2_2") (pintype "passive"))
      (node (ref "U8") (pin "1") (pinfunction "IN+_1") (pintype "input"))
    )
    (net (code "39") (name "Net-(U8-IN-)") (class "Default")
      (node (ref "R43") (pin "1") (pinfunction "1_1") (pintype "passive"))
      (node (ref "U8") (pin "3") (pinfunction "IN-_3") (pintype "input"))
      (node (ref "U8") (pin "4") (pinfunction "OUT_4") (pintype "output"))
    )
    (net (code "40") (name "Net-(U9-HB)") (class "Default")
      (node (ref "R51") (pin "2") (pinfunction "2_2") (pintype "passive"))
      (node (ref "U9") (pin "10") (pinfunction "HB_10") (pintype "power_in"))
    )
    (net (code "41") (name "Net-(U9-HI)") (class "Default")
      (node (ref "C77") (pin "1") (pinfunction "1_1") (pintype "passive"))
      (node (ref "R52") (pin "2") (pinfunction "2_2") (pintype "passive"))
      (node (ref "R53") (pin "2") (pinfunction "2_2") (pintype "passive"))
      (node (ref "U9") (pin "12") (pinfunction "HI_12") (pintype "input"))
    )
    (net (code "42") (name "Net-(U9-HS)") (class "Default")
      (node (ref "C73") (pin "2") (pinfunction "2_2") (pintype "passive"))
      (node (ref "U9") (pin "11") (pinfunction "HS_11") (pintype "power_in"))
    )
    (net (code "43") (name "Net-(U9-LI)") (class "Default")
      (node (ref "C79") (pin "1") (pinfunction "1_1") (pintype "passive"))
      (node (ref "R54") (pin "2") (pinfunction "2_2") (pintype "passive"))
      (node (ref "R55") (pin "2") (pinfunction "2_2") (pintype "passive"))
      (node (ref "U9") (pin "13") (pinfunction "LI_13") (pintype "input"))
    )
    (net (code "44") (name "Net-(U9-SW)") (class "Default")
      (node (ref "C56") (pin "2") (pinfunction "2_2") (pintype "passive"))
      (node (ref "C61") (pin "2") (pinfunction "2_2") (pintype "passive"))
      (node (ref "C70") (pin "2") (pinfunction "2_2") (pintype "passive"))
      (node (ref "C71") (pin "2") (pinfunction "2_2") (pintype "passive"))
      (node (ref "C74") (pin "2") (pinfunction "2_2") (pintype "passive"))
      (node (ref "C75") (pin "2") (pinfunction "2_2") (pintype "passive"))
      (node (ref "C76") (pin "2") (pinfunction "2_2") (pintype "passive"))
      (node (ref "C78") (pin "2") (pinfunction "2_2") (pintype "passive"))
      (node (ref "TP49") (pin "1") (pintype "passive"))
      (node (ref "U9") (pin "5") (pinfunction "SW_5") (pintype "power_in"))
    )
    (net (code "45") (name "Net-(U9-VCC)") (class "Default")
      (node (ref "R50") (pin "2") (pinfunction "2_2") (pintype "passive"))
      (node (ref "U9") (pin "14") (pinfunction "VCC_14") (pintype "power_in"))
    )
    (net (code "46") (name "PGND_LV") (class "Default")
      (node (ref "C222") (pin "2") (pinfunction "N_2") (pintype "passive"))
      (node (ref "C39") (pin "1") (pinfunction "1_1") (pintype "passive"))
      (node (ref "C40") (pin "1") (pinfunction "1_1") (pintype "passive"))
      (node (ref "C41") (pin "2") (pinfunction "2_2") (pintype "passive"))
      (node (ref "C42") (pin "2") (pinfunction "2_2") (pintype "passive"))
      (node (ref "C57") (pin "1") (pinfunction "1_1") (pintype "passive"))
      (node (ref "C58") (pin "1") (pinfunction "1_1") (pintype "passive"))
      (node (ref "C59") (pin "2") (pinfunction "2_2") (pintype "passive"))
      (node (ref "C60") (pin "2") (pinfunction "2_2") (pintype "passive"))
      (node (ref "J14") (pin "1") (pinfunction "1_1") (pintype "passive"))
      (node (ref "TP10") (pin "1") (pintype "passive"))
      (node (ref "TP54") (pin "1") (pintype "passive"))
      (node (ref "U7") (pin "6") (pinfunction "PGND_6") (pintype "power_in"))
      (node (ref "U9") (pin "6") (pinfunction "PGND_6") (pintype "power_in"))
    )
    (net (code "47") (name "unconnected-(J12-MNT_1-Pad2)") (class "Default")
      (node (ref "J12") (pin "2") (pinfunction "MNT_1_2") (pintype "passive"))
    )
    (net (code "48") (name "unconnected-(J12-MNT_2-Pad3)") (class "Default")
      (node (ref "J12") (pin "3") (pinfunction "MNT_2_3") (pintype "passive"))
    )
    (net (code "49") (name "unconnected-(J12-MNT_3-Pad4)") (class "Default")
      (node (ref "J12") (pin "4") (pinfunction "MNT_3_4") (pintype "passive"))
    )
    (net (code "50") (name "unconnected-(J12-MNT_4-Pad5)") (class "Default")
      (node (ref "J12") (pin "5") (pinfunction "MNT_4_5") (pintype "passive"))
    )
    (net (code "51") (name "unconnected-(J13-MNT_1-Pad2)") (class "Default")
      (node (ref "J13") (pin "2") (pinfunction "MNT_1_2") (pintype "passive"))
    )
    (net (code "52") (name "unconnected-(J13-MNT_2-Pad3)") (class "Default")
      (node (ref "J13") (pin "3") (pinfunction "MNT_2_3") (pintype "passive"))
    )
    (net (code "53") (name "unconnected-(J13-MNT_3-Pad4)") (class "Default")
      (node (ref "J13") (pin "4") (pinfunction "MNT_3_4") (pintype "passive"))
    )
    (net (code "54") (name "unconnected-(J13-MNT_4-Pad5)") (class "Default")
      (node (ref "J13") (pin "5") (pinfunction "MNT_4_5") (pintype "passive"))
    )
    (net (code "55") (name "unconnected-(J14-MNT_1-Pad2)") (class "Default")
      (node (ref "J14") (pin "2") (pinfunction "MNT_1_2") (pintype "passive"))
    )
    (net (code "56") (name "unconnected-(J14-MNT_2-Pad3)") (class "Default")
      (node (ref "J14") (pin "3") (pinfunction "MNT_2_3") (pintype "passive"))
    )
    (net (code "57") (name "unconnected-(J14-MNT_3-Pad4)") (class "Default")
      (node (ref "J14") (pin "4") (pinfunction "MNT_3_4") (pintype "passive"))
    )
    (net (code "58") (name "unconnected-(J14-MNT_4-Pad5)") (class "Default")
      (node (ref "J14") (pin "5") (pinfunction "MNT_4_5") (pintype "passive"))
    )
    (net (code "59") (name "unconnected-(J15-MNT_1-Pad2)") (class "Default")
      (node (ref "J15") (pin "2") (pinfunction "MNT_1_2") (pintype "passive"))
    )
    (net (code "60") (name "unconnected-(J15-MNT_2-Pad3)") (class "Default")
      (node (ref "J15") (pin "3") (pinfunction "MNT_2_3") (pintype "passive"))
    )
    (net (code "61") (name "unconnected-(J15-MNT_3-Pad4)") (class "Default")
      (node (ref "J15") (pin "4") (pinfunction "MNT_3_4") (pintype "passive"))
    )
    (net (code "62") (name "unconnected-(J15-MNT_4-Pad5)") (class "Default")
      (node (ref "J15") (pin "5") (pinfunction "MNT_4_5") (pintype "passive"))
    )
    (net (code "63") (name "unconnected-(U5-NC-Pad5)") (class "Default")
      (node (ref "U5") (pin "5") (pinfunction "NC_5") (pintype "passive"))
    )
    (net (code "64") (name "unconnected-(U5-VOC-Pad8)") (class "Default")
      (node (ref "U5") (pin "8") (pinfunction "VOC_8") (pintype "passive"))
    )
    (net (code "65") (name "unconnected-(U5-~{FAULT}-Pad4)") (class "Default")
      (node (ref "U5") (pin "4") (pinfunction "~{FAULT}_4") (pintype "output"))
    )
    (net (code "66") (name "unconnected-(U5-~{OC}-Pad7)") (class "Default")
      (node (ref "U5") (pin "7") (pinfunction "~{OC}_7") (pintype "open_collector"))
    )
    (net (code "67") (name "unconnected-(U6-NC-Pad5)") (class "Default")
      (node (ref "U6") (pin "5") (pinfunction "NC_5") (pintype "passive"))
    )
    (net (code "68") (name "unconnected-(U6-VOC-Pad8)") (class "Default")
      (node (ref "U6") (pin "8") (pinfunction "VOC_8") (pintype "passive"))
    )
    (net (code "69") (name "unconnected-(U6-~{FAULT}-Pad4)") (class "Default")
      (node (ref "U6") (pin "4") (pinfunction "~{FAULT}_4") (pintype "output"))
    )
    (net (code "70") (name "unconnected-(U6-~{OC}-Pad7)") (class "Default")
      (node (ref "U6") (pin "7") (pinfunction "~{OC}_7") (pintype "open_collector"))
    )
    (net (code "71") (name "unconnected-(U7-NC-Pad1)") (class "Default")
      (node (ref "U7") (pin "1") (pinfunction "NC_1") (pintype "passive+no_connect"))
    )
    (net (code "72") (name "unconnected-(U7-NC-Pad2)") (class "Default")
      (node (ref "U7") (pin "2") (pinfunction "NC_2") (pintype "passive+no_connect"))
    )
    (net (code "73") (name "unconnected-(U7-NC-Pad3)") (class "Default")
      (node (ref "U7") (pin "3") (pinfunction "NC_3") (pintype "passive+no_connect"))
    )
    (net (code "74") (name "unconnected-(U7-NC-Pad4)") (class "Default")
      (node (ref "U7") (pin "4") (pinfunction "NC_4") (pintype "passive+no_connect"))
    )
    (net (code "75") (name "unconnected-(U7-NC-Pad8)") (class "Default")
      (node (ref "U7") (pin "8") (pinfunction "NC_8") (pintype "passive+no_connect"))
    )
    (net (code "76") (name "unconnected-(U7-NC-Pad9)") (class "Default")
      (node (ref "U7") (pin "9") (pinfunction "NC_9") (pintype "passive+no_connect"))
    )
    (net (code "77") (name "unconnected-(U7-NC-Pad16)") (class "Default")
      (node (ref "U7") (pin "16") (pinfunction "NC_16") (pintype "passive+no_connect"))
    )
    (net (code "78") (name "unconnected-(U9-NC-Pad1)") (class "Default")
      (node (ref "U9") (pin "1") (pinfunction "NC_1") (pintype "passive+no_connect"))
    )
    (net (code "79") (name "unconnected-(U9-NC-Pad2)") (class "Default")
      (node (ref "U9") (pin "2") (pinfunction "NC_2") (pintype "passive+no_connect"))
    )
    (net (code "80") (name "unconnected-(U9-NC-Pad3)") (class "Default")
      (node (ref "U9") (pin "3") (pinfunction "NC_3") (pintype "passive+no_connect"))
    )
    (net (code "81") (name "unconnected-(U9-NC-Pad4)") (class "Default")
      (node (ref "U9") (pin "4") (pinfunction "NC_4") (pintype "passive+no_connect"))
    )
    (net (code "82") (name "unconnected-(U9-NC-Pad8)") (class "Default")
      (node (ref "U9") (pin "8") (pinfunction "NC_8") (pintype "passive+no_connect"))
    )
    (net (code "83") (name "unconnected-(U9-NC-Pad9)") (class "Default")
      (node (ref "U9") (pin "9") (pinfunction "NC_9") (pintype "passive+no_connect"))
    )
    (net (code "84") (name "unconnected-(U9-NC-Pad16)") (class "Default")
      (node (ref "U9") (pin "16") (pinfunction "NC_16") (pintype "passive+no_connect"))
    )
  )
)
